# 5_dac.net
KiCad netlist of a schematic drawn in Altium Designer
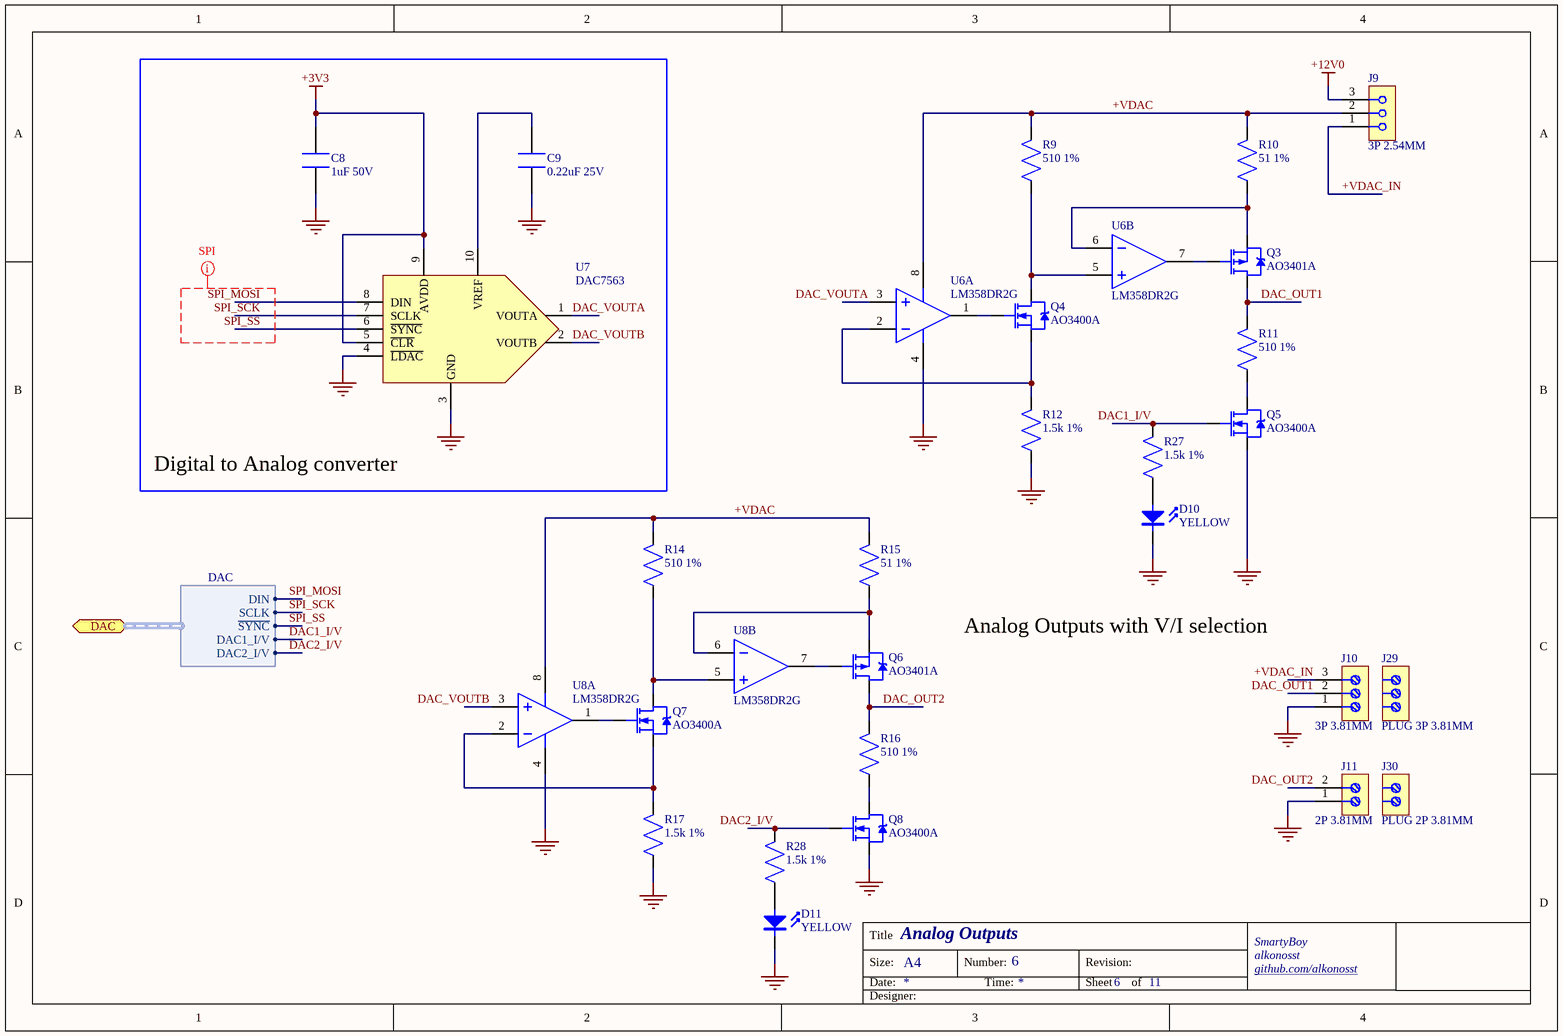
[diagram p0: 5_dac.SchDoc]

(export (version "E")
  (design (tool "Eeschema 10.0.6"))
  (components
    (comp (ref "C8")
      (value "1uF 50V")
      (footprint "C0603")
      (description "X5R ±10% 50V 1uF 0603 Multilayer Ceramic Capacitors MLCC - SMD/SMT")
      (fields (field (name "LCSC PART") "C15849"))
      (libsource (lib "nombre_por_definir") (part "CL10A105KB8NNNC"))
    )
    (comp (ref "C9")
      (value "0.22uF 25V")
      (footprint "C0603")
      (description "X7R 25V ±10% 220nF 0603 Multilayer Ceramic Capacitors MLCC - SMD/SMT")
      (fields (field (name "LCSC PART") "C21120"))
      (libsource (lib "nombre_por_definir") (part "CL10B224KA8NNNC"))
    )
    (comp (ref "D10")
      (value "YELLOW")
      (footprint "LED0603-YELLOW")
      (description "Yellow 585.5~591.5nm 0603 Light Emitting Diodes (LED)")
      (fields (field (name "LCSC PART") "C72038"))
      (libsource (lib "nombre_por_definir") (part "19-213/Y2C-CQ2R2L/3T(CY)"))
    )
    (comp (ref "D11")
      (value "YELLOW")
      (footprint "LED0603-YELLOW")
      (description "Yellow 585.5~591.5nm 0603 Light Emitting Diodes (LED)")
      (fields (field (name "LCSC PART") "C72038"))
      (libsource (lib "nombre_por_definir") (part "19-213/Y2C-CQ2R2L/3T(CY)"))
    )
    (comp (ref "J9")
      (value "3P 2.54MM")
      (footprint "HDR-M-3P-2.54MM")
      (description "3 2.54mm Straight 1 Header，Breakaway Through Hole Pin Header & Female Header")
      (fields (field (name "LCSC PART") "C49257"))
      (libsource (lib "nombre_por_definir") (part "C49257"))
    )
    (comp (ref "J10")
      (value "3P 3.81MM")
      (footprint "TB-3P-3.81MM")
      (description "Terminal Block 3 Positions 3.81MM")
      (libsource (lib "nombre_por_definir") (part "TBLOCK-3P-3.81MM"))
    )
    (comp (ref "J11")
      (value "2P 3.81MM")
      (footprint "TB-2P-3.81MM")
      (description "Terminal Block 2 Positions 3.81MM")
      (libsource (lib "nombre_por_definir") (part "TBLOCK-2P-3.81MM"))
    )
    (comp (ref "J29")
      (value "PLUG 3P 3.81MM")
      (footprint "TB-PLUG-3P-3.81MM")
      (description "Terminal block plug 3positions 3.81mm")
      (libsource (lib "nombre_por_definir") (part "PLUG-3P-3.81MM"))
    )
    (comp (ref "J30")
      (value "PLUG 2P 3.81MM")
      (footprint "TB-PLUG-2P-3.81MM")
      (description "Terminal block plug 2positions 3.81mm")
      (libsource (lib "nombre_por_definir") (part "PLUG-2P-3.81MM"))
    )
    (comp (ref "Q3")
      (value "AO3401A")
      (footprint "SOT-23-3")
      (description "1.4W 0.044Ω 4.3A,10V 30V 1.3V 250uA P Channel 4A SOT-23-3L MOSFETs")
      (fields (field (name "LCSC PART") "C15127"))
      (libsource (lib "nombre_por_definir") (part "AO3401A"))
    )
    (comp (ref "Q4")
      (value "AO3400A")
      (footprint "SOT-23-3")
      (description "1.4W 0.0265Ω 5.7A,10V 30V 5.7A N Channel 1.5V 250uA SOT-23-3L MOSFETs")
      (fields (field (name "LCSC PART") "C20917"))
      (libsource (lib "nombre_por_definir") (part "AO3400A"))
    )
    (comp (ref "Q5")
      (value "AO3400A")
      (footprint "SOT-23-3")
      (description "1.4W 0.0265Ω 5.7A,10V 30V 5.7A N Channel 1.5V 250uA SOT-23-3L MOSFETs")
      (fields (field (name "LCSC PART") "C20917"))
      (libsource (lib "nombre_por_definir") (part "AO3400A"))
    )
    (comp (ref "Q6")
      (value "AO3401A")
      (footprint "SOT-23-3")
      (description "1.4W 0.044Ω 4.3A,10V 30V 1.3V 250uA P Channel 4A SOT-23-3L MOSFETs")
      (fields (field (name "LCSC PART") "C15127"))
      (libsource (lib "nombre_por_definir") (part "AO3401A"))
    )
    (comp (ref "Q7")
      (value "AO3400A")
      (footprint "SOT-23-3")
      (description "1.4W 0.0265Ω 5.7A,10V 30V 5.7A N Channel 1.5V 250uA SOT-23-3L MOSFETs")
      (fields (field (name "LCSC PART") "C20917"))
      (libsource (lib "nombre_por_definir") (part "AO3400A"))
    )
    (comp (ref "Q8")
      (value "AO3400A")
      (footprint "SOT-23-3")
      (description "1.4W 0.0265Ω 5.7A,10V 30V 5.7A N Channel 1.5V 250uA SOT-23-3L MOSFETs")
      (fields (field (name "LCSC PART") "C20917"))
      (libsource (lib "nombre_por_definir") (part "AO3400A"))
    )
    (comp (ref "R9")
      (value "510 1%")
      (footprint "R0603")
      (description "510Ω ±1% ±100ppm/℃ 0.1W 0603 Chip Resistor - Surface Mount")
      (fields (field (name "LCSC PART") "C23193"))
      (libsource (lib "nombre_por_definir") (part "0603WAF5100T5E"))
    )
    (comp (ref "R10")
      (value "51 1%")
      (footprint "R0603")
      (description "±1% ±200ppm/℃ 0.1W 51Ω 0603 Chip Resistor - Surface Mount")
      (fields (field (name "LCSC PART") "C23197"))
      (libsource (lib "nombre_por_definir") (part "0603WAF510JT5E"))
    )
    (comp (ref "R11")
      (value "510 1%")
      (footprint "R0603")
      (description "510Ω ±1% ±100ppm/℃ 0.1W 0603 Chip Resistor - Surface Mount")
      (fields (field (name "LCSC PART") "C23193"))
      (libsource (lib "nombre_por_definir") (part "0603WAF5100T5E"))
    )
    (comp (ref "R12")
      (value "1.5k 1%")
      (footprint "R0603")
      (description "1.5kΩ ±1% ±100ppm/℃ 0.1W 0603 Chip Resistor - Surface Mount")
      (fields (field (name "LCSC PART") "C22843"))
      (libsource (lib "nombre_por_definir") (part "0603WAF1501T5E"))
    )
    (comp (ref "R14")
      (value "510 1%")
      (footprint "R0603")
      (description "510Ω ±1% ±100ppm/℃ 0.1W 0603 Chip Resistor - Surface Mount")
      (fields (field (name "LCSC PART") "C23193"))
      (libsource (lib "nombre_por_definir") (part "0603WAF5100T5E"))
    )
    (comp (ref "R15")
      (value "51 1%")
      (footprint "R0603")
      (description "±1% ±200ppm/℃ 0.1W 51Ω 0603 Chip Resistor - Surface Mount")
      (fields (field (name "LCSC PART") "C23197"))
      (libsource (lib "nombre_por_definir") (part "0603WAF510JT5E"))
    )
    (comp (ref "R16")
      (value "510 1%")
      (footprint "R0603")
      (description "510Ω ±1% ±100ppm/℃ 0.1W 0603 Chip Resistor - Surface Mount")
      (fields (field (name "LCSC PART") "C23193"))
      (libsource (lib "nombre_por_definir") (part "0603WAF5100T5E"))
    )
    (comp (ref "R17")
      (value "1.5k 1%")
      (footprint "R0603")
      (description "1.5kΩ ±1% ±100ppm/℃ 0.1W 0603 Chip Resistor - Surface Mount")
      (fields (field (name "LCSC PART") "C22843"))
      (libsource (lib "nombre_por_definir") (part "0603WAF1501T5E"))
    )
    (comp (ref "R27")
      (value "1.5k 1%")
      (footprint "R0603")
      (description "1.5kΩ ±1% ±100ppm/℃ 0.1W 0603 Chip Resistor - Surface Mount")
      (fields (field (name "LCSC PART") "C22843"))
      (libsource (lib "nombre_por_definir") (part "0603WAF1501T5E"))
    )
    (comp (ref "R28")
      (value "1.5k 1%")
      (footprint "R0603")
      (description "1.5kΩ ±1% ±100ppm/℃ 0.1W 0603 Chip Resistor - Surface Mount")
      (fields (field (name "LCSC PART") "C22843"))
      (libsource (lib "nombre_por_definir") (part "0603WAF1501T5E"))
    )
    (comp (ref "U6")
      (value "LM358DR2G")
      (footprint "SOIC-8")
      (fields (field (name "LCSC PART") "C7950"))
      (libsource (lib "nombre_por_definir") (part "LM358DR2G"))
    )
    (comp (ref "U7")
      (value "DAC7563")
      (footprint "VSSOP-10")
      (description "VSSOP-10 Digital To Analog Converters (DACs)")
      (fields (field (name "LCSC PART") "C601656"))
      (libsource (lib "nombre_por_definir") (part "DAC7563SDGSR"))
    )
    (comp (ref "U8")
      (value "LM358DR2G")
      (footprint "SOIC-8")
      (fields (field (name "LCSC PART") "C7950"))
      (libsource (lib "nombre_por_definir") (part "LM358DR2G"))
    )
  )
  (nets
    (net (code "2") (name "+3V3") (class "Default")
      (node (ref "C8") (pin "1") (pinfunction "1_1") (pintype "passive"))
      (node (ref "U7") (pin "5") (pinfunction "~{CLR}_5") (pintype "passive"))
      (node (ref "U7") (pin "9") (pinfunction "AVDD_9") (pintype "passive"))
    )
    (net (code "3") (name "+12V0") (class "Default")
      (node (ref "J9") (pin "3") (pinfunction "3_3") (pintype "passive"))
    )
    (net (code "4") (name "/+VDAC") (class "Default")
      (node (ref "J9") (pin "2") (pinfunction "2_2") (pintype "passive"))
      (node (ref "R10") (pin "2") (pinfunction "2_2") (pintype "passive"))
      (node (ref "R14") (pin "2") (pinfunction "2_2") (pintype "passive"))
      (node (ref "R15") (pin "2") (pinfunction "2_2") (pintype "passive"))
      (node (ref "R9") (pin "2") (pinfunction "2_2") (pintype "passive"))
      (node (ref "U6") (pin "8") (pinfunction "VDD_8") (pintype "power_in"))
      (node (ref "U8") (pin "8") (pinfunction "VDD_8") (pintype "power_in"))
    )
    (net (code "5") (name "/+VDAC_IN") (class "Default")
      (node (ref "J10") (pin "3") (pinfunction "3_3") (pintype "passive"))
      (node (ref "J9") (pin "1") (pinfunction "1_1") (pintype "passive"))
    )
    (net (code "6") (name "/DAC1_I{slash}V") (class "Default")
      (node (ref "Q5") (pin "1") (pinfunction "G_1") (pintype "passive"))
      (node (ref "R27") (pin "2") (pinfunction "2_2") (pintype "passive"))
    )
    (net (code "7") (name "/DAC2_I{slash}V") (class "Default")
      (node (ref "Q8") (pin "1") (pinfunction "G_1") (pintype "passive"))
      (node (ref "R28") (pin "2") (pinfunction "2_2") (pintype "passive"))
    )
    (net (code "8") (name "/DAC_OUT1") (class "Default")
      (node (ref "J10") (pin "2") (pinfunction "2_2") (pintype "passive"))
      (node (ref "Q3") (pin "3") (pinfunction "D_3") (pintype "passive"))
      (node (ref "R11") (pin "2") (pinfunction "2_2") (pintype "passive"))
    )
    (net (code "9") (name "/DAC_OUT2") (class "Default")
      (node (ref "J11") (pin "2") (pinfunction "2_2") (pintype "passive"))
      (node (ref "Q6") (pin "3") (pinfunction "D_3") (pintype "passive"))
      (node (ref "R16") (pin "2") (pinfunction "2_2") (pintype "passive"))
    )
    (net (code "10") (name "/DAC_VOUTA") (class "Default")
      (node (ref "U6") (pin "3") (pinfunction "IN1+_3") (pintype "passive"))
      (node (ref "U7") (pin "1") (pinfunction "VOUTA_1") (pintype "passive"))
    )
    (net (code "11") (name "/DAC_VOUTB") (class "Default")
      (node (ref "U7") (pin "2") (pinfunction "VOUTB_2") (pintype "passive"))
      (node (ref "U8") (pin "3") (pinfunction "IN1+_3") (pintype "passive"))
    )
    (net (code "12") (name "/SPI_MOSI") (class "Default")
      (node (ref "U7") (pin "8") (pinfunction "DIN_8") (pintype "passive"))
    )
    (net (code "13") (name "/SPI_SCK") (class "Default")
      (node (ref "U7") (pin "7") (pinfunction "SCLK_7") (pintype "passive"))
    )
    (net (code "14") (name "/SPI_SS") (class "Default")
      (node (ref "U7") (pin "6") (pinfunction "~{SYNC}_6") (pintype "passive"))
    )
    (net (code "16") (name "GND") (class "Default")
      (node (ref "C8") (pin "2") (pinfunction "2_2") (pintype "passive"))
      (node (ref "C9") (pin "2") (pinfunction "2_2") (pintype "passive"))
      (node (ref "D10") (pin "1") (pinfunction "1_1") (pintype "passive"))
      (node (ref "D11") (pin "1") (pinfunction "1_1") (pintype "passive"))
      (node (ref "J10") (pin "1") (pinfunction "1_1") (pintype "passive"))
      (node (ref "J11") (pin "1") (pinfunction "1_1") (pintype "passive"))
      (node (ref "Q5") (pin "2") (pinfunction "S_2") (pintype "passive"))
      (node (ref "Q8") (pin "2") (pinfunction "S_2") (pintype "passive"))
      (node (ref "R12") (pin "1") (pinfunction "1_1") (pintype "passive"))
      (node (ref "R17") (pin "1") (pinfunction "1_1") (pintype "passive"))
      (node (ref "U6") (pin "4") (pinfunction "VSS_4") (pintype "power_in"))
      (node (ref "U7") (pin "3") (pinfunction "GND_3") (pintype "passive"))
      (node (ref "U7") (pin "4") (pinfunction "~{LDAC}_4") (pintype "passive"))
      (node (ref "U8") (pin "4") (pinfunction "VSS_4") (pintype "power_in"))
    )
    (net (code "17") (name "Net-(D10-Pad2)") (class "Default")
      (node (ref "D10") (pin "2") (pinfunction "2_2") (pintype "passive"))
      (node (ref "R27") (pin "1") (pinfunction "1_1") (pintype "passive"))
    )
    (net (code "18") (name "Net-(D11-Pad2)") (class "Default")
      (node (ref "D11") (pin "2") (pinfunction "2_2") (pintype "passive"))
      (node (ref "R28") (pin "1") (pinfunction "1_1") (pintype "passive"))
    )
    (net (code "19") (name "Net-(Q3-G)") (class "Default")
      (node (ref "Q3") (pin "1") (pinfunction "G_1") (pintype "passive"))
      (node (ref "U6") (pin "7") (pinfunction "OUT2_7") (pintype "passive"))
    )
    (net (code "20") (name "Net-(Q3-S)") (class "Default")
      (node (ref "Q3") (pin "2") (pinfunction "S_2") (pintype "passive"))
      (node (ref "R10") (pin "1") (pinfunction "1_1") (pintype "passive"))
      (node (ref "U6") (pin "6") (pinfunction "IN2-_6") (pintype "passive"))
    )
    (net (code "21") (name "Net-(Q4-D)") (class "Default")
      (node (ref "Q4") (pin "3") (pinfunction "D_3") (pintype "passive"))
      (node (ref "R9") (pin "1") (pinfunction "1_1") (pintype "passive"))
      (node (ref "U6") (pin "5") (pinfunction "IN2+_5") (pintype "passive"))
    )
    (net (code "22") (name "Net-(Q4-G)") (class "Default")
      (node (ref "Q4") (pin "1") (pinfunction "G_1") (pintype "passive"))
      (node (ref "U6") (pin "1") (pinfunction "OUT1_1") (pintype "passive"))
    )
    (net (code "23") (name "Net-(Q4-S)") (class "Default")
      (node (ref "Q4") (pin "2") (pinfunction "S_2") (pintype "passive"))
      (node (ref "R12") (pin "2") (pinfunction "2_2") (pintype "passive"))
      (node (ref "U6") (pin "2") (pinfunction "IN1-_2") (pintype "passive"))
    )
    (net (code "24") (name "Net-(Q5-D)") (class "Default")
      (node (ref "Q5") (pin "3") (pinfunction "D_3") (pintype "passive"))
      (node (ref "R11") (pin "1") (pinfunction "1_1") (pintype "passive"))
    )
    (net (code "25") (name "Net-(Q6-G)") (class "Default")
      (node (ref "Q6") (pin "1") (pinfunction "G_1") (pintype "passive"))
      (node (ref "U8") (pin "7") (pinfunction "OUT2_7") (pintype "passive"))
    )
    (net (code "26") (name "Net-(Q6-S)") (class "Default")
      (node (ref "Q6") (pin "2") (pinfunction "S_2") (pintype "passive"))
      (node (ref "R15") (pin "1") (pinfunction "1_1") (pintype "passive"))
      (node (ref "U8") (pin "6") (pinfunction "IN2-_6") (pintype "passive"))
    )
    (net (code "27") (name "Net-(Q7-D)") (class "Default")
      (node (ref "Q7") (pin "3") (pinfunction "D_3") (pintype "passive"))
      (node (ref "R14") (pin "1") (pinfunction "1_1") (pintype "passive"))
      (node (ref "U8") (pin "5") (pinfunction "IN2+_5") (pintype "passive"))
    )
    (net (code "28") (name "Net-(Q7-G)") (class "Default")
      (node (ref "Q7") (pin "1") (pinfunction "G_1") (pintype "passive"))
      (node (ref "U8") (pin "1") (pinfunction "OUT1_1") (pintype "passive"))
    )
    (net (code "29") (name "Net-(Q7-S)") (class "Default")
      (node (ref "Q7") (pin "2") (pinfunction "S_2") (pintype "passive"))
      (node (ref "R17") (pin "2") (pinfunction "2_2") (pintype "passive"))
      (node (ref "U8") (pin "2") (pinfunction "IN1-_2") (pintype "passive"))
    )
    (net (code "30") (name "Net-(Q8-D)") (class "Default")
      (node (ref "Q8") (pin "3") (pinfunction "D_3") (pintype "passive"))
      (node (ref "R16") (pin "1") (pinfunction "1_1") (pintype "passive"))
    )
    (net (code "31") (name "Net-(U7-VREF)") (class "Default")
      (node (ref "C9") (pin "1") (pinfunction "1_1") (pintype "passive"))
      (node (ref "U7") (pin "10") (pinfunction "VREF_10") (pintype "passive"))
    )
  )
)
